# Flash.net
KiCad netlist of a schematic drawn in Altium Designer
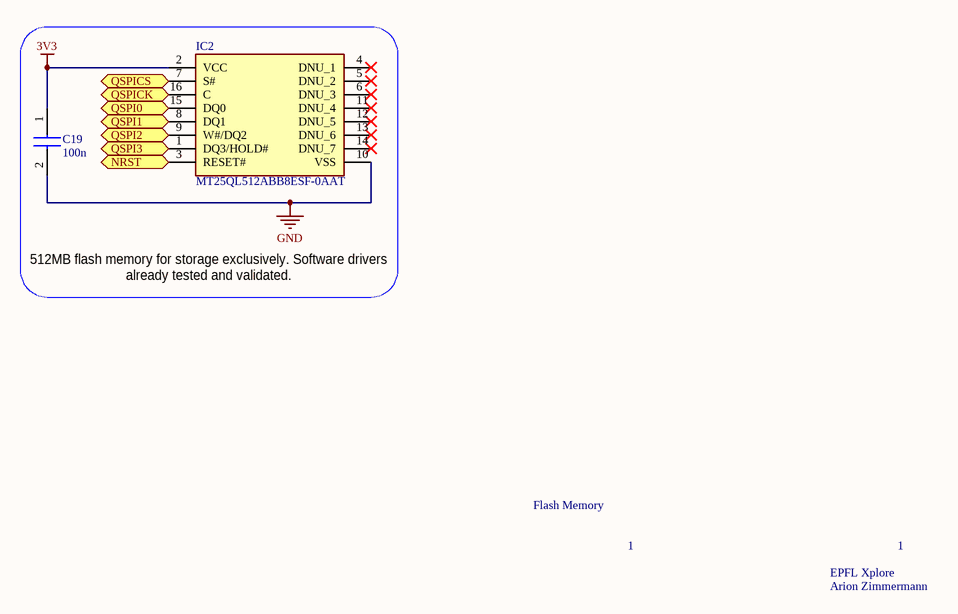
[diagram p0: Flash.SchDoc]

(export (version "E")
  (design (tool "Eeschema 10.0.6"))
  (components
    (comp (ref "C19")
      (value "100n")
      (footprint "SamacSys:CAPC1608X95N")
      (description "Capacitor")
      (fields
        (field (name "MANUFACTURER_PART_NUMBER") "C0603C104K5RACTU")
        (field (name "MOUSER PART NUMBER") "80-C0603C104K5R")
      )
      (libsource (lib "CarrierBoard") (part "C0603C104K5RACTU"))
    )
    (comp (ref "IC2")
      (value "MT25QL512ABB8ESF-0AAT")
      (footprint "SamacSys:SOIC127P1032X265-16N")
      (description "Integrated Circuit")
      (fields (field (name "MOUSER PART NUMBER") "340-285789-TRAY"))
      (libsource (lib "CarrierBoard") (part "MT25QL512ABB8ESF-0AAT"))
    )
  )
  (nets
    (net (code "1") (name "/NRST") (class "Default")
      (node (ref "IC2") (pin "3") (pinfunction "RESET#_3") (pintype "passive"))
    )
    (net (code "2") (name "/QSPI0") (class "Default")
      (node (ref "IC2") (pin "15") (pinfunction "DQ0_15") (pintype "passive"))
    )
    (net (code "3") (name "/QSPI1") (class "Default")
      (node (ref "IC2") (pin "8") (pinfunction "DQ1_8") (pintype "passive"))
    )
    (net (code "4") (name "/QSPI2") (class "Default")
      (node (ref "IC2") (pin "9") (pinfunction "W#/DQ2_9") (pintype "passive"))
    )
    (net (code "5") (name "/QSPI3") (class "Default")
      (node (ref "IC2") (pin "1") (pinfunction "DQ3/HOLD#_1") (pintype "passive"))
    )
    (net (code "6") (name "/QSPICK") (class "Default")
      (node (ref "IC2") (pin "16") (pinfunction "C_16") (pintype "passive"))
    )
    (net (code "7") (name "/QSPICS") (class "Default")
      (node (ref "IC2") (pin "7") (pinfunction "S#_7") (pintype "passive"))
    )
    (net (code "8") (name "3V3") (class "Default")
      (node (ref "C19") (pin "1") (pinfunction "1_1") (pintype "passive"))
      (node (ref "IC2") (pin "2") (pinfunction "VCC_2") (pintype "passive"))
    )
    (net (code "9") (name "GND") (class "Default")
      (node (ref "C19") (pin "2") (pinfunction "2_2") (pintype "passive"))
      (node (ref "IC2") (pin "10") (pinfunction "VSS_10") (pintype "passive"))
    )
    (net (code "10") (name "unconnected-(IC2-DNU_1-Pad4)") (class "Default")
      (node (ref "IC2") (pin "4") (pinfunction "DNU_1_4") (pintype "passive+no_connect"))
    )
    (net (code "11") (name "unconnected-(IC2-DNU_2-Pad5)") (class "Default")
      (node (ref "IC2") (pin "5") (pinfunction "DNU_2_5") (pintype "passive+no_connect"))
    )
    (net (code "12") (name "unconnected-(IC2-DNU_3-Pad6)") (class "Default")
      (node (ref "IC2") (pin "6") (pinfunction "DNU_3_6") (pintype "passive+no_connect"))
    )
    (net (code "13") (name "unconnected-(IC2-DNU_4-Pad11)") (class "Default")
      (node (ref "IC2") (pin "11") (pinfunction "DNU_4_11") (pintype "passive+no_connect"))
    )
    (net (code "14") (name "unconnected-(IC2-DNU_5-Pad12)") (class "Default")
      (node (ref "IC2") (pin "12") (pinfunction "DNU_5_12") (pintype "passive+no_connect"))
    )
    (net (code "15") (name "unconnected-(IC2-DNU_6-Pad13)") (class "Default")
      (node (ref "IC2") (pin "13") (pinfunction "DNU_6_13") (pintype "passive+no_connect"))
    )
    (net (code "16") (name "unconnected-(IC2-DNU_7-Pad14)") (class "Default")
      (node (ref "IC2") (pin "14") (pinfunction "DNU_7_14") (pintype "passive+no_connect"))
    )
  )
)
